# Interface.net
KiCad netlist of a schematic drawn in Altium Designer
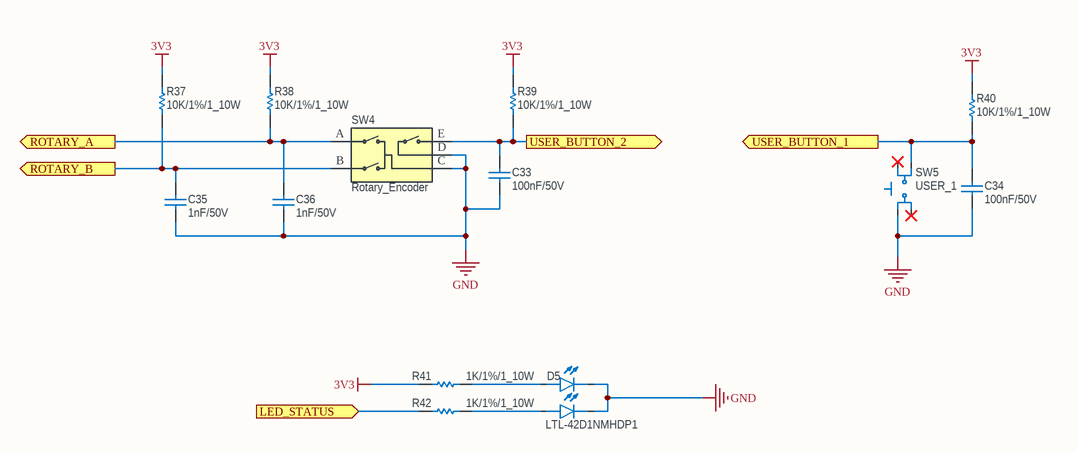
[diagram p0: Interface.SchDoc]

(export (version "E")
  (design (tool "Eeschema 10.0.6"))
  (components
    (comp (ref "C33")
      (value "100nF/50V")
      (footprint "CAP_0603")
      (description "CAP, size 0603, 100nF, 50V")
      (fields (field (name "SUPPLY PART NUMBER") "Tụ Gốm 0603 100nF (0.1uF) 50V"))
      (libsource (lib "BluetoothTracking") (part "Ceramic_Cap_100nF_50V_0603"))
    )
    (comp (ref "C34")
      (value "100nF/50V")
      (footprint "CAP_0603")
      (description "CAP, size 0603, 100nF, 50V")
      (fields (field (name "SUPPLY PART NUMBER") "Tụ Gốm 0603 100nF (0.1uF) 50V"))
      (libsource (lib "BluetoothTracking") (part "Ceramic_Cap_100nF_50V_0603"))
    )
    (comp (ref "C35")
      (value "1nF/50V")
      (footprint "CAP_0603")
      (description "CAP, size 0603, 1nF, 50V")
      (fields (field (name "SUPPLY PART NUMBER") "CC0603KRX7R9BB102"))
      (libsource (lib "BluetoothTracking") (part "Ceramic_Cap_1nF_50V_0603"))
    )
    (comp (ref "C36")
      (value "1nF/50V")
      (footprint "CAP_0603")
      (description "CAP, size 0603, 1nF, 50V")
      (fields (field (name "SUPPLY PART NUMBER") "CC0603KRX7R9BB102"))
      (libsource (lib "BluetoothTracking") (part "Ceramic_Cap_1nF_50V_0603"))
    )
    (comp (ref "D5")
      (value "LTL-42D1NMHDP1")
      (footprint "LTL42D1NMHDP1")
      (description "2 LED 3mm, xuyên lỗ")
      (fields (field (name "SUPPLY PART NUMBER") "Bộ Chỉ Thị 2 LED Xanh lá-Đỏ 3mm Đế Nhựa Hàn PCB"))
      (libsource (lib "BluetoothTracking") (part "LTL-42D1NMHDP1"))
    )
    (comp (ref "R37")
      (value "10K/1%/1_10W")
      (footprint "Resistor_0603")
      (description "Resistor 0603 10KOhm 1% 1_10W")
      (fields (field (name "SUPPLY PART NUMBER") "Điện Trở 10 KOhm 0603 1%"))
      (libsource (lib "BluetoothTracking") (part "Res_10K_0603_1%"))
    )
    (comp (ref "R38")
      (value "10K/1%/1_10W")
      (footprint "Resistor_0603")
      (description "Resistor 0603 10KOhm 1% 1_10W")
      (fields (field (name "SUPPLY PART NUMBER") "Điện Trở 10 KOhm 0603 1%"))
      (libsource (lib "BluetoothTracking") (part "Res_10K_0603_1%"))
    )
    (comp (ref "R39")
      (value "10K/1%/1_10W")
      (footprint "Resistor_0603")
      (description "Resistor 0603 10KOhm 1% 1_10W")
      (fields (field (name "SUPPLY PART NUMBER") "Điện Trở 10 KOhm 0603 1%"))
      (libsource (lib "BluetoothTracking") (part "Res_10K_0603_1%"))
    )
    (comp (ref "R40")
      (value "10K/1%/1_10W")
      (footprint "Resistor_0603")
      (description "Resistor 0603 10KOhm 1% 1_10W")
      (fields (field (name "SUPPLY PART NUMBER") "Điện Trở 10 KOhm 0603 1%"))
      (libsource (lib "BluetoothTracking") (part "Res_10K_0603_1%"))
    )
    (comp (ref "R41")
      (value "1K/1%/1_10W")
      (footprint "Resistor_0603")
      (description "Resistor 0603 1KOhm 1% 1_10W")
      (fields (field (name "SUPPLY PART NUMBER") "Điện Trở 1 KOhm 0603 1%"))
      (libsource (lib "BluetoothTracking") (part "Res_1K_0603_1%"))
    )
    (comp (ref "R42")
      (value "1K/1%/1_10W")
      (footprint "Resistor_0603")
      (description "Resistor 0603 1KOhm 1% 1_10W")
      (fields (field (name "SUPPLY PART NUMBER") "Điện Trở 1 KOhm 0603 1%"))
      (libsource (lib "BluetoothTracking") (part "Res_1K_0603_1%"))
    )
    (comp (ref "SW4")
      (value "Rotary_Encoder")
      (footprint "EC11E_AAL")
      (description "No Description Available")
      (fields (field (name "SUPPLY PART NUMBER") "EC11 Rotary Encoder 20 Vị Trí 15mm"))
      (libsource (lib "BluetoothTracking") (part "Rotary_Encoder"))
    )
    (comp (ref "SW5")
      (value "USER_1")
      (footprint "SW_B3F-4050_OMR")
      (description "No Description Available")
      (fields (field (name "SUPPLY PART NUMBER") "B3F-4055 Nút Nhấn 12x12mm Cao 7.3mm 4 Chân Xuyên Lỗ Omron"))
      (libsource (lib "BluetoothTracking") (part "Button_B3F-4055"))
    )
  )
  (nets
    (net (code "1") (name "/LED_STATUS") (class "Default")
      (node (ref "R42") (pin "1") (pinfunction "1_1") (pintype "passive"))
    )
    (net (code "2") (name "/ROTARY_A") (class "Default")
      (node (ref "C36") (pin "2") (pinfunction "2_2") (pintype "passive"))
      (node (ref "R38") (pin "1") (pinfunction "1_1") (pintype "passive"))
      (node (ref "SW4") (pin "A") (pinfunction "A_A") (pintype "passive"))
    )
    (net (code "3") (name "/ROTARY_B") (class "Default")
      (node (ref "C35") (pin "2") (pinfunction "2_2") (pintype "passive"))
      (node (ref "R37") (pin "1") (pinfunction "1_1") (pintype "passive"))
      (node (ref "SW4") (pin "B") (pinfunction "B_B") (pintype "passive"))
    )
    (net (code "4") (name "/USER_BUTTON_1") (class "Default")
      (node (ref "C34") (pin "2") (pinfunction "2_2") (pintype "passive"))
      (node (ref "R40") (pin "1") (pinfunction "1_1") (pintype "passive"))
      (node (ref "SW5") (pin "2") (pinfunction "2_2") (pintype "passive"))
    )
    (net (code "5") (name "/USER_BUTTON_2") (class "Default")
      (node (ref "C33") (pin "2") (pinfunction "2_2") (pintype "passive"))
      (node (ref "R39") (pin "1") (pinfunction "1_1") (pintype "passive"))
      (node (ref "SW4") (pin "E") (pinfunction "E_E") (pintype "passive"))
    )
    (net (code "6") (name "3V3") (class "Default")
      (node (ref "R37") (pin "2") (pinfunction "2_2") (pintype "passive"))
      (node (ref "R38") (pin "2") (pinfunction "2_2") (pintype "passive"))
      (node (ref "R39") (pin "2") (pinfunction "2_2") (pintype "passive"))
      (node (ref "R40") (pin "2") (pinfunction "2_2") (pintype "passive"))
      (node (ref "R41") (pin "1") (pinfunction "1_1") (pintype "passive"))
    )
    (net (code "7") (name "GND") (class "Default")
      (node (ref "C33") (pin "1") (pinfunction "1_1") (pintype "passive"))
      (node (ref "C34") (pin "1") (pinfunction "1_1") (pintype "passive"))
      (node (ref "C35") (pin "1") (pinfunction "1_1") (pintype "passive"))
      (node (ref "C36") (pin "1") (pinfunction "1_1") (pintype "passive"))
      (node (ref "D5") (pin "1") (pinfunction "K_1_1") (pintype "passive"))
      (node (ref "D5") (pin "3") (pinfunction "K_2_3") (pintype "passive"))
      (node (ref "SW4") (pin "C") (pinfunction "C_C") (pintype "passive"))
      (node (ref "SW4") (pin "D") (pinfunction "D_D") (pintype "passive"))
      (node (ref "SW5") (pin "3") (pinfunction "3_3") (pintype "passive"))
    )
    (net (code "8") (name "Net-(D5-A_1)") (class "Default")
      (node (ref "D5") (pin "2") (pinfunction "A_1_2") (pintype "passive"))
      (node (ref "R41") (pin "2") (pinfunction "2_2") (pintype "passive"))
    )
    (net (code "9") (name "Net-(D5-A_2)") (class "Default")
      (node (ref "D5") (pin "4") (pinfunction "A_2_4") (pintype "passive"))
      (node (ref "R42") (pin "2") (pinfunction "2_2") (pintype "passive"))
    )
    (net (code "10") (name "unconnected-(SW5-Pad1)") (class "Default")
      (node (ref "SW5") (pin "1") (pinfunction "1_1") (pintype "passive+no_connect"))
    )
    (net (code "11") (name "unconnected-(SW5-Pad4)") (class "Default")
      (node (ref "SW5") (pin "4") (pinfunction "4_4") (pintype "passive+no_connect"))
    )
  )
)
